# hub.net
KiCad netlist of a schematic drawn in EAGLE
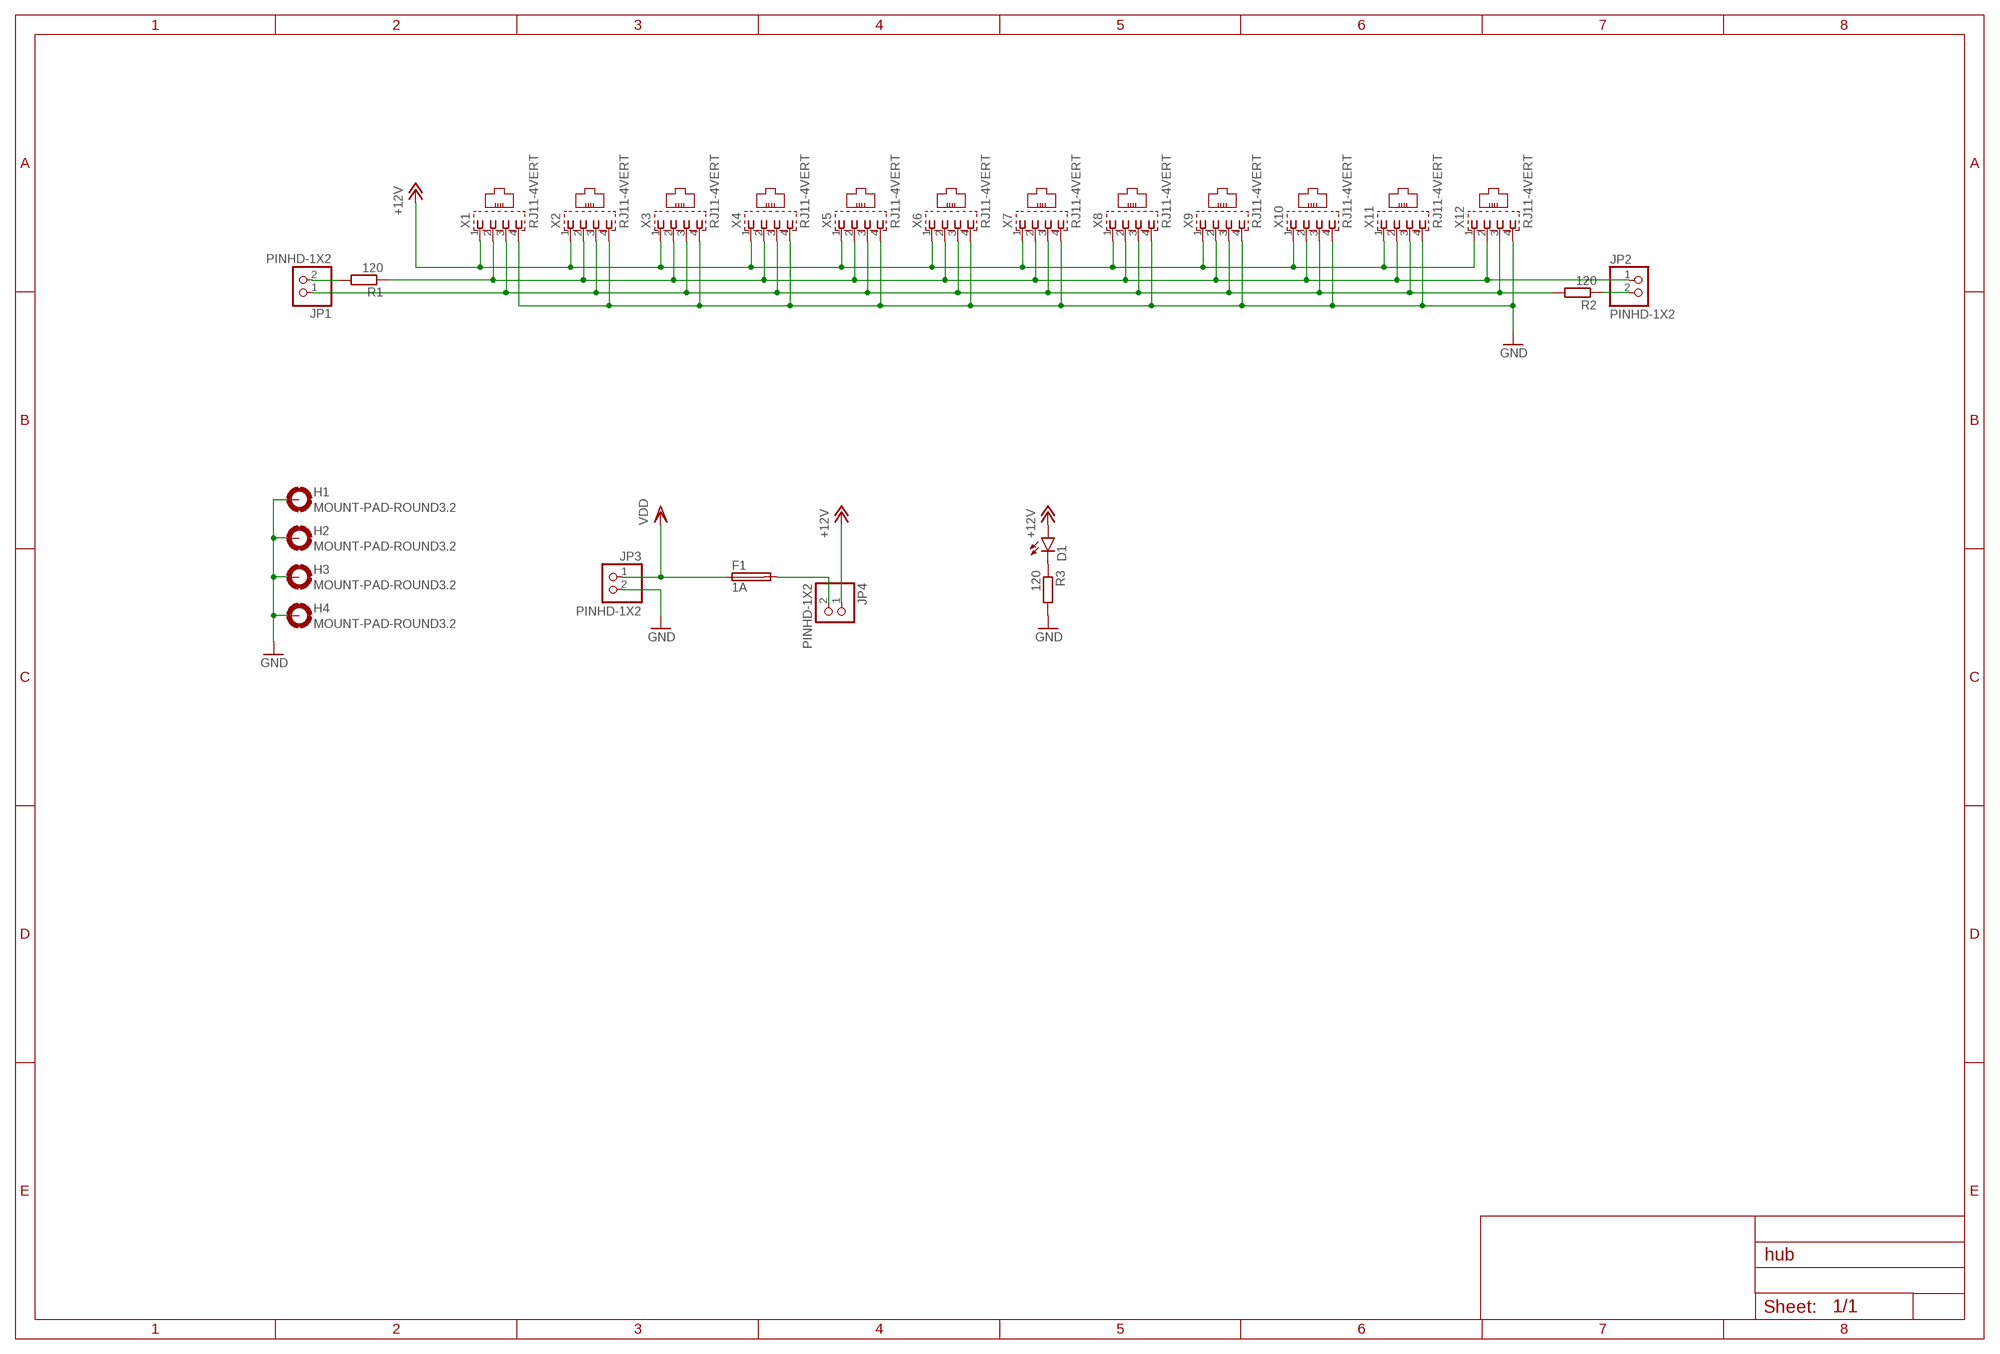
[diagram p0: schematic, sheet 1]

(export (version "E")
  (design (tool "Eeschema 10.0.6"))
  (components
    (comp (ref "D1")
      (value "LED1206")
      (footprint "eagle-import:CHIPLED_1206")
      (libsource (lib "eagle-import") (part "LED1206"))
    )
    (comp (ref "F1")
      (value "1A")
      (footprint "eagle-import:5X20_FUSE")
      (libsource (lib "eagle-import") (part "5X20_FUSE"))
    )
    (comp (ref "H1")
      (value "MOUNT-PAD-ROUND3.2")
      (footprint "eagle-import:3,2-PAD")
      (libsource (lib "eagle-import") (part "MOUNT-PAD-ROUND3.2"))
    )
    (comp (ref "H2")
      (value "MOUNT-PAD-ROUND3.2")
      (footprint "eagle-import:3,2-PAD")
      (libsource (lib "eagle-import") (part "MOUNT-PAD-ROUND3.2"))
    )
    (comp (ref "H3")
      (value "MOUNT-PAD-ROUND3.2")
      (footprint "eagle-import:3,2-PAD")
      (libsource (lib "eagle-import") (part "MOUNT-PAD-ROUND3.2"))
    )
    (comp (ref "H4")
      (value "MOUNT-PAD-ROUND3.2")
      (footprint "eagle-import:3,2-PAD")
      (libsource (lib "eagle-import") (part "MOUNT-PAD-ROUND3.2"))
    )
    (comp (ref "JP1")
      (value "PINHD-1X2")
      (footprint "eagle-import:1X02")
      (libsource (lib "eagle-import") (part "PINHD-1X2"))
    )
    (comp (ref "JP2")
      (value "PINHD-1X2")
      (footprint "eagle-import:1X02")
      (libsource (lib "eagle-import") (part "PINHD-1X2"))
    )
    (comp (ref "JP3")
      (value "PINHD-1X2")
      (footprint "eagle-import:1X02")
      (libsource (lib "eagle-import") (part "PINHD-1X2"))
    )
    (comp (ref "JP4")
      (value "PINHD-1X2")
      (footprint "eagle-import:1X02")
      (libsource (lib "eagle-import") (part "PINHD-1X2"))
    )
    (comp (ref "R1")
      (value "120")
      (footprint "eagle-import:R0805")
      (libsource (lib "eagle-import") (part "RESISTOR0805"))
    )
    (comp (ref "R2")
      (value "120")
      (footprint "eagle-import:R0805")
      (libsource (lib "eagle-import") (part "RESISTOR0805"))
    )
    (comp (ref "R3")
      (value "120")
      (footprint "eagle-import:R0805")
      (libsource (lib "eagle-import") (part "RESISTOR0805"))
    )
    (comp (ref "X1")
      (value "RJ11-4VERT")
      (footprint "eagle-import:RJ11-4_VERT")
      (libsource (lib "eagle-import") (part "RJ11-4VERT"))
    )
    (comp (ref "X2")
      (value "RJ11-4VERT")
      (footprint "eagle-import:RJ11-4_VERT")
      (libsource (lib "eagle-import") (part "RJ11-4VERT"))
    )
    (comp (ref "X3")
      (value "RJ11-4VERT")
      (footprint "eagle-import:RJ11-4_VERT")
      (libsource (lib "eagle-import") (part "RJ11-4VERT"))
    )
    (comp (ref "X4")
      (value "RJ11-4VERT")
      (footprint "eagle-import:RJ11-4_VERT")
      (libsource (lib "eagle-import") (part "RJ11-4VERT"))
    )
    (comp (ref "X5")
      (value "RJ11-4VERT")
      (footprint "eagle-import:RJ11-4_VERT")
      (libsource (lib "eagle-import") (part "RJ11-4VERT"))
    )
    (comp (ref "X6")
      (value "RJ11-4VERT")
      (footprint "eagle-import:RJ11-4_VERT")
      (libsource (lib "eagle-import") (part "RJ11-4VERT"))
    )
    (comp (ref "X7")
      (value "RJ11-4VERT")
      (footprint "eagle-import:RJ11-4_VERT")
      (libsource (lib "eagle-import") (part "RJ11-4VERT"))
    )
    (comp (ref "X8")
      (value "RJ11-4VERT")
      (footprint "eagle-import:RJ11-4_VERT")
      (libsource (lib "eagle-import") (part "RJ11-4VERT"))
    )
    (comp (ref "X9")
      (value "RJ11-4VERT")
      (footprint "eagle-import:RJ11-4_VERT")
      (libsource (lib "eagle-import") (part "RJ11-4VERT"))
    )
    (comp (ref "X10")
      (value "RJ11-4VERT")
      (footprint "eagle-import:RJ11-4_VERT")
      (libsource (lib "eagle-import") (part "RJ11-4VERT"))
    )
    (comp (ref "X11")
      (value "RJ11-4VERT")
      (footprint "eagle-import:RJ11-4_VERT")
      (libsource (lib "eagle-import") (part "RJ11-4VERT"))
    )
    (comp (ref "X12")
      (value "RJ11-4VERT")
      (footprint "eagle-import:RJ11-4_VERT")
      (libsource (lib "eagle-import") (part "RJ11-4VERT"))
    )
  )
  (nets
    (net (code "1") (name "+12V") (class "Default")
      (node (ref "D1") (pin "A") (pinfunction "A_A") (pintype "passive"))
      (node (ref "JP4") (pin "1") (pinfunction "1_1") (pintype "passive"))
      (node (ref "X1") (pin "1") (pinfunction "1_1") (pintype "passive"))
      (node (ref "X10") (pin "1") (pinfunction "1_1") (pintype "passive"))
      (node (ref "X11") (pin "1") (pinfunction "1_1") (pintype "passive"))
      (node (ref "X12") (pin "1") (pinfunction "1_1") (pintype "passive"))
      (node (ref "X2") (pin "1") (pinfunction "1_1") (pintype "passive"))
      (node (ref "X3") (pin "1") (pinfunction "1_1") (pintype "passive"))
      (node (ref "X4") (pin "1") (pinfunction "1_1") (pintype "passive"))
      (node (ref "X5") (pin "1") (pinfunction "1_1") (pintype "passive"))
      (node (ref "X6") (pin "1") (pinfunction "1_1") (pintype "passive"))
      (node (ref "X7") (pin "1") (pinfunction "1_1") (pintype "passive"))
      (node (ref "X8") (pin "1") (pinfunction "1_1") (pintype "passive"))
      (node (ref "X9") (pin "1") (pinfunction "1_1") (pintype "passive"))
    )
    (net (code "2") (name "GND") (class "Default")
      (node (ref "H1") (pin "B3,2") (pinfunction "MOUNT_B3,2") (pintype "passive"))
      (node (ref "H1") (pin "P$1") (pinfunction "MOUNT_P$1") (pintype "passive"))
      (node (ref "H1") (pin "P$2") (pinfunction "MOUNT_P$2") (pintype "passive"))
      (node (ref "H1") (pin "P$3") (pinfunction "MOUNT_P$3") (pintype "passive"))
      (node (ref "H1") (pin "P$4") (pinfunction "MOUNT_P$4") (pintype "passive"))
      (node (ref "H1") (pin "P$5") (pinfunction "MOUNT_P$5") (pintype "passive"))
      (node (ref "H1") (pin "P$6") (pinfunction "MOUNT_P$6") (pintype "passive"))
      (node (ref "H1") (pin "P$7") (pinfunction "MOUNT_P$7") (pintype "passive"))
      (node (ref "H1") (pin "P$8") (pinfunction "MOUNT_P$8") (pintype "passive"))
      (node (ref "H2") (pin "B3,2") (pinfunction "MOUNT_B3,2") (pintype "passive"))
      (node (ref "H2") (pin "P$1") (pinfunction "MOUNT_P$1") (pintype "passive"))
      (node (ref "H2") (pin "P$2") (pinfunction "MOUNT_P$2") (pintype "passive"))
      (node (ref "H2") (pin "P$3") (pinfunction "MOUNT_P$3") (pintype "passive"))
      (node (ref "H2") (pin "P$4") (pinfunction "MOUNT_P$4") (pintype "passive"))
      (node (ref "H2") (pin "P$5") (pinfunction "MOUNT_P$5") (pintype "passive"))
      (node (ref "H2") (pin "P$6") (pinfunction "MOUNT_P$6") (pintype "passive"))
      (node (ref "H2") (pin "P$7") (pinfunction "MOUNT_P$7") (pintype "passive"))
      (node (ref "H2") (pin "P$8") (pinfunction "MOUNT_P$8") (pintype "passive"))
      (node (ref "H3") (pin "B3,2") (pinfunction "MOUNT_B3,2") (pintype "passive"))
      (node (ref "H3") (pin "P$1") (pinfunction "MOUNT_P$1") (pintype "passive"))
      (node (ref "H3") (pin "P$2") (pinfunction "MOUNT_P$2") (pintype "passive"))
      (node (ref "H3") (pin "P$3") (pinfunction "MOUNT_P$3") (pintype "passive"))
      (node (ref "H3") (pin "P$4") (pinfunction "MOUNT_P$4") (pintype "passive"))
      (node (ref "H3") (pin "P$5") (pinfunction "MOUNT_P$5") (pintype "passive"))
      (node (ref "H3") (pin "P$6") (pinfunction "MOUNT_P$6") (pintype "passive"))
      (node (ref "H3") (pin "P$7") (pinfunction "MOUNT_P$7") (pintype "passive"))
      (node (ref "H3") (pin "P$8") (pinfunction "MOUNT_P$8") (pintype "passive"))
      (node (ref "H4") (pin "B3,2") (pinfunction "MOUNT_B3,2") (pintype "passive"))
      (node (ref "H4") (pin "P$1") (pinfunction "MOUNT_P$1") (pintype "passive"))
      (node (ref "H4") (pin "P$2") (pinfunction "MOUNT_P$2") (pintype "passive"))
      (node (ref "H4") (pin "P$3") (pinfunction "MOUNT_P$3") (pintype "passive"))
      (node (ref "H4") (pin "P$4") (pinfunction "MOUNT_P$4") (pintype "passive"))
      (node (ref "H4") (pin "P$5") (pinfunction "MOUNT_P$5") (pintype "passive"))
      (node (ref "H4") (pin "P$6") (pinfunction "MOUNT_P$6") (pintype "passive"))
      (node (ref "H4") (pin "P$7") (pinfunction "MOUNT_P$7") (pintype "passive"))
      (node (ref "H4") (pin "P$8") (pinfunction "MOUNT_P$8") (pintype "passive"))
      (node (ref "JP3") (pin "2") (pinfunction "2_2") (pintype "passive"))
      (node (ref "R3") (pin "2") (pinfunction "2_2") (pintype "passive"))
      (node (ref "X1") (pin "4") (pinfunction "4_4") (pintype "passive"))
      (node (ref "X10") (pin "4") (pinfunction "4_4") (pintype "passive"))
      (node (ref "X11") (pin "4") (pinfunction "4_4") (pintype "passive"))
      (node (ref "X12") (pin "4") (pinfunction "4_4") (pintype "passive"))
      (node (ref "X2") (pin "4") (pinfunction "4_4") (pintype "passive"))
      (node (ref "X3") (pin "4") (pinfunction "4_4") (pintype "passive"))
      (node (ref "X4") (pin "4") (pinfunction "4_4") (pintype "passive"))
      (node (ref "X5") (pin "4") (pinfunction "4_4") (pintype "passive"))
      (node (ref "X6") (pin "4") (pinfunction "4_4") (pintype "passive"))
      (node (ref "X7") (pin "4") (pinfunction "4_4") (pintype "passive"))
      (node (ref "X8") (pin "4") (pinfunction "4_4") (pintype "passive"))
      (node (ref "X9") (pin "4") (pinfunction "4_4") (pintype "passive"))
    )
    (net (code "3") (name "Net-(D1-PadC)") (class "Default")
      (node (ref "D1") (pin "C") (pinfunction "C_C") (pintype "passive"))
      (node (ref "R3") (pin "1") (pinfunction "1_1") (pintype "passive"))
    )
    (net (code "4") (name "Net-(F1-2-Pad2A)") (class "Default")
      (node (ref "F1") (pin "2A") (pinfunction "2_2A") (pintype "passive"))
      (node (ref "F1") (pin "2B") (pinfunction "2_2B") (pintype "passive"))
      (node (ref "JP4") (pin "2") (pinfunction "2_2") (pintype "passive"))
    )
    (net (code "5") (name "Net-(JP1-Pad1)") (class "Default")
      (node (ref "JP1") (pin "1") (pinfunction "1_1") (pintype "passive"))
      (node (ref "R2") (pin "2") (pinfunction "2_2") (pintype "passive"))
      (node (ref "X1") (pin "3") (pinfunction "3_3") (pintype "passive"))
      (node (ref "X10") (pin "3") (pinfunction "3_3") (pintype "passive"))
      (node (ref "X11") (pin "3") (pinfunction "3_3") (pintype "passive"))
      (node (ref "X12") (pin "3") (pinfunction "3_3") (pintype "passive"))
      (node (ref "X2") (pin "3") (pinfunction "3_3") (pintype "passive"))
      (node (ref "X3") (pin "3") (pinfunction "3_3") (pintype "passive"))
      (node (ref "X4") (pin "3") (pinfunction "3_3") (pintype "passive"))
      (node (ref "X5") (pin "3") (pinfunction "3_3") (pintype "passive"))
      (node (ref "X6") (pin "3") (pinfunction "3_3") (pintype "passive"))
      (node (ref "X7") (pin "3") (pinfunction "3_3") (pintype "passive"))
      (node (ref "X8") (pin "3") (pinfunction "3_3") (pintype "passive"))
      (node (ref "X9") (pin "3") (pinfunction "3_3") (pintype "passive"))
    )
    (net (code "6") (name "Net-(JP1-Pad2)") (class "Default")
      (node (ref "JP1") (pin "2") (pinfunction "2_2") (pintype "passive"))
      (node (ref "R1") (pin "2") (pinfunction "2_2") (pintype "passive"))
    )
    (net (code "7") (name "Net-(JP2-Pad1)") (class "Default")
      (node (ref "JP2") (pin "1") (pinfunction "1_1") (pintype "passive"))
      (node (ref "R1") (pin "1") (pinfunction "1_1") (pintype "passive"))
      (node (ref "X1") (pin "2") (pinfunction "2_2") (pintype "passive"))
      (node (ref "X10") (pin "2") (pinfunction "2_2") (pintype "passive"))
      (node (ref "X11") (pin "2") (pinfunction "2_2") (pintype "passive"))
      (node (ref "X12") (pin "2") (pinfunction "2_2") (pintype "passive"))
      (node (ref "X2") (pin "2") (pinfunction "2_2") (pintype "passive"))
      (node (ref "X3") (pin "2") (pinfunction "2_2") (pintype "passive"))
      (node (ref "X4") (pin "2") (pinfunction "2_2") (pintype "passive"))
      (node (ref "X5") (pin "2") (pinfunction "2_2") (pintype "passive"))
      (node (ref "X6") (pin "2") (pinfunction "2_2") (pintype "passive"))
      (node (ref "X7") (pin "2") (pinfunction "2_2") (pintype "passive"))
      (node (ref "X8") (pin "2") (pinfunction "2_2") (pintype "passive"))
      (node (ref "X9") (pin "2") (pinfunction "2_2") (pintype "passive"))
    )
    (net (code "8") (name "Net-(JP2-Pad2)") (class "Default")
      (node (ref "JP2") (pin "2") (pinfunction "2_2") (pintype "passive"))
      (node (ref "R2") (pin "1") (pinfunction "1_1") (pintype "passive"))
    )
    (net (code "9") (name "VDD") (class "Default")
      (node (ref "F1") (pin "1A") (pinfunction "1_1A") (pintype "passive"))
      (node (ref "F1") (pin "1B") (pinfunction "1_1B") (pintype "passive"))
      (node (ref "JP3") (pin "1") (pinfunction "1_1") (pintype "passive"))
    )
  )
)
